# phyplugin.net
KiCad netlist of a schematic drawn in EAGLE
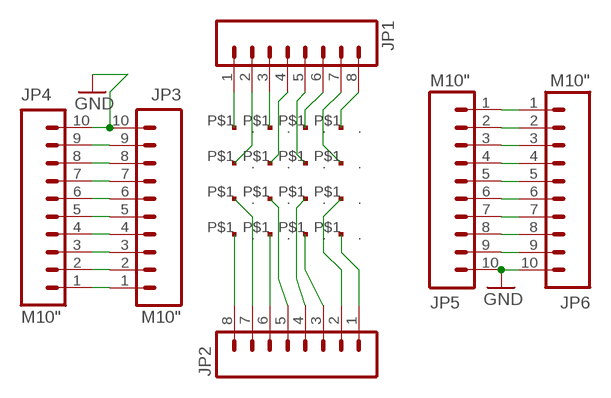
[diagram p0: schematic, sheet 1]

(export (version "E")
  (design (tool "Eeschema 10.0.6"))
  (components
    (comp (ref "JP1")
      (value "M08")
      (footprint "eagle-import:1X08")
      (libsource (lib "eagle-import") (part "M08"))
    )
    (comp (ref "JP2")
      (value "M08")
      (footprint "eagle-import:1X08")
      (libsource (lib "eagle-import") (part "M08"))
    )
    (comp (ref "JP3")
      (value "M10\"")
      (footprint "eagle-import:1X10")
      (libsource (lib "eagle-import") (part "M10{dblquote}"))
    )
    (comp (ref "JP4")
      (value "M10\"")
      (footprint "eagle-import:1X10")
      (libsource (lib "eagle-import") (part "M10{dblquote}"))
    )
    (comp (ref "JP5")
      (value "M10\"")
      (footprint "eagle-import:1X10")
      (libsource (lib "eagle-import") (part "M10{dblquote}"))
    )
    (comp (ref "JP6")
      (value "M10\"")
      (footprint "eagle-import:1X10")
      (libsource (lib "eagle-import") (part "M10{dblquote}"))
    )
    (comp (ref "U$1")
      (value "MEAPAD")
      (footprint "eagle-import:MEAPAD1MM")
      (libsource (lib "eagle-import") (part "MEAPAD"))
    )
    (comp (ref "U$2")
      (value "MEAPAD")
      (footprint "eagle-import:MEAPAD1MM")
      (libsource (lib "eagle-import") (part "MEAPAD"))
    )
    (comp (ref "U$3")
      (value "MEAPAD")
      (footprint "eagle-import:MEAPAD1MM")
      (libsource (lib "eagle-import") (part "MEAPAD"))
    )
    (comp (ref "U$4")
      (value "MEAPAD")
      (footprint "eagle-import:MEAPAD1MM")
      (libsource (lib "eagle-import") (part "MEAPAD"))
    )
    (comp (ref "U$5")
      (value "MEAPAD")
      (footprint "eagle-import:MEAPAD1MM")
      (libsource (lib "eagle-import") (part "MEAPAD"))
    )
    (comp (ref "U$6")
      (value "MEAPAD")
      (footprint "eagle-import:MEAPAD1MM")
      (libsource (lib "eagle-import") (part "MEAPAD"))
    )
    (comp (ref "U$7")
      (value "MEAPAD")
      (footprint "eagle-import:MEAPAD1MM")
      (libsource (lib "eagle-import") (part "MEAPAD"))
    )
    (comp (ref "U$8")
      (value "MEAPAD")
      (footprint "eagle-import:MEAPAD1MM")
      (libsource (lib "eagle-import") (part "MEAPAD"))
    )
    (comp (ref "U$9")
      (value "MEAPAD")
      (footprint "eagle-import:MEAPAD1MM")
      (libsource (lib "eagle-import") (part "MEAPAD"))
    )
    (comp (ref "U$10")
      (value "MEAPAD")
      (footprint "eagle-import:MEAPAD1MM")
      (libsource (lib "eagle-import") (part "MEAPAD"))
    )
    (comp (ref "U$11")
      (value "MEAPAD")
      (footprint "eagle-import:MEAPAD1MM")
      (libsource (lib "eagle-import") (part "MEAPAD"))
    )
    (comp (ref "U$12")
      (value "MEAPAD")
      (footprint "eagle-import:MEAPAD1MM")
      (libsource (lib "eagle-import") (part "MEAPAD"))
    )
    (comp (ref "U$13")
      (value "MEAPAD")
      (footprint "eagle-import:MEAPAD1MM")
      (libsource (lib "eagle-import") (part "MEAPAD"))
    )
    (comp (ref "U$14")
      (value "MEAPAD")
      (footprint "eagle-import:MEAPAD1MM")
      (libsource (lib "eagle-import") (part "MEAPAD"))
    )
    (comp (ref "U$15")
      (value "MEAPAD")
      (footprint "eagle-import:MEAPAD1MM")
      (libsource (lib "eagle-import") (part "MEAPAD"))
    )
    (comp (ref "U$16")
      (value "MEAPAD")
      (footprint "eagle-import:MEAPAD1MM")
      (libsource (lib "eagle-import") (part "MEAPAD"))
    )
  )
  (nets
    (net (code "1") (name "GND") (class "Default")
      (node (ref "JP3") (pin "10") (pinfunction "10_10") (pintype "passive"))
      (node (ref "JP4") (pin "10") (pinfunction "10_10") (pintype "passive"))
      (node (ref "JP5") (pin "10") (pinfunction "10_10") (pintype "passive"))
      (node (ref "JP6") (pin "10") (pinfunction "10_10") (pintype "passive"))
    )
    (net (code "2") (name "Net-(JP3-Pad1)") (class "Default")
      (node (ref "JP3") (pin "1") (pinfunction "1_1") (pintype "passive"))
      (node (ref "JP4") (pin "1") (pinfunction "1_1") (pintype "passive"))
    )
    (net (code "3") (name "Net-(JP3-Pad2)") (class "Default")
      (node (ref "JP3") (pin "2") (pinfunction "2_2") (pintype "passive"))
      (node (ref "JP4") (pin "2") (pinfunction "2_2") (pintype "passive"))
    )
    (net (code "4") (name "Net-(JP3-Pad3)") (class "Default")
      (node (ref "JP3") (pin "3") (pinfunction "3_3") (pintype "passive"))
      (node (ref "JP4") (pin "3") (pinfunction "3_3") (pintype "passive"))
    )
    (net (code "5") (name "Net-(JP3-Pad4)") (class "Default")
      (node (ref "JP3") (pin "4") (pinfunction "4_4") (pintype "passive"))
      (node (ref "JP4") (pin "4") (pinfunction "4_4") (pintype "passive"))
    )
    (net (code "6") (name "Net-(JP3-Pad5)") (class "Default")
      (node (ref "JP3") (pin "5") (pinfunction "5_5") (pintype "passive"))
      (node (ref "JP4") (pin "5") (pinfunction "5_5") (pintype "passive"))
    )
    (net (code "7") (name "Net-(JP3-Pad6)") (class "Default")
      (node (ref "JP3") (pin "6") (pinfunction "6_6") (pintype "passive"))
      (node (ref "JP4") (pin "6") (pinfunction "6_6") (pintype "passive"))
    )
    (net (code "8") (name "Net-(JP3-Pad7)") (class "Default")
      (node (ref "JP3") (pin "7") (pinfunction "7_7") (pintype "passive"))
      (node (ref "JP4") (pin "7") (pinfunction "7_7") (pintype "passive"))
    )
    (net (code "9") (name "Net-(JP3-Pad8)") (class "Default")
      (node (ref "JP3") (pin "8") (pinfunction "8_8") (pintype "passive"))
      (node (ref "JP4") (pin "8") (pinfunction "8_8") (pintype "passive"))
    )
    (net (code "10") (name "Net-(JP3-Pad9)") (class "Default")
      (node (ref "JP3") (pin "9") (pinfunction "9_9") (pintype "passive"))
      (node (ref "JP4") (pin "9") (pinfunction "9_9") (pintype "passive"))
    )
    (net (code "11") (name "Net-(JP5-Pad1)") (class "Default")
      (node (ref "JP5") (pin "1") (pinfunction "1_1") (pintype "passive"))
      (node (ref "JP6") (pin "1") (pinfunction "1_1") (pintype "passive"))
    )
    (net (code "12") (name "Net-(JP5-Pad2)") (class "Default")
      (node (ref "JP5") (pin "2") (pinfunction "2_2") (pintype "passive"))
      (node (ref "JP6") (pin "2") (pinfunction "2_2") (pintype "passive"))
    )
    (net (code "13") (name "Net-(JP5-Pad3)") (class "Default")
      (node (ref "JP5") (pin "3") (pinfunction "3_3") (pintype "passive"))
      (node (ref "JP6") (pin "3") (pinfunction "3_3") (pintype "passive"))
    )
    (net (code "14") (name "Net-(JP5-Pad4)") (class "Default")
      (node (ref "JP5") (pin "4") (pinfunction "4_4") (pintype "passive"))
      (node (ref "JP6") (pin "4") (pinfunction "4_4") (pintype "passive"))
    )
    (net (code "15") (name "Net-(JP5-Pad5)") (class "Default")
      (node (ref "JP5") (pin "5") (pinfunction "5_5") (pintype "passive"))
      (node (ref "JP6") (pin "5") (pinfunction "5_5") (pintype "passive"))
    )
    (net (code "16") (name "Net-(JP5-Pad6)") (class "Default")
      (node (ref "JP5") (pin "6") (pinfunction "6_6") (pintype "passive"))
      (node (ref "JP6") (pin "6") (pinfunction "6_6") (pintype "passive"))
    )
    (net (code "17") (name "Net-(JP5-Pad7)") (class "Default")
      (node (ref "JP5") (pin "7") (pinfunction "7_7") (pintype "passive"))
      (node (ref "JP6") (pin "7") (pinfunction "7_7") (pintype "passive"))
    )
    (net (code "18") (name "Net-(JP5-Pad8)") (class "Default")
      (node (ref "JP5") (pin "8") (pinfunction "8_8") (pintype "passive"))
      (node (ref "JP6") (pin "8") (pinfunction "8_8") (pintype "passive"))
    )
    (net (code "19") (name "Net-(JP5-Pad9)") (class "Default")
      (node (ref "JP5") (pin "9") (pinfunction "9_9") (pintype "passive"))
      (node (ref "JP6") (pin "9") (pinfunction "9_9") (pintype "passive"))
    )
    (net (code "20") (name "Net-(U$1-.)") (class "Default")
      (node (ref "JP1") (pin "1") (pinfunction "1_1") (pintype "passive"))
      (node (ref "U$1") (pin "P$1") (pinfunction "._P$1") (pintype "bidirectional"))
    )
    (net (code "21") (name "Net-(U$2-.)") (class "Default")
      (node (ref "JP1") (pin "3") (pinfunction "3_3") (pintype "passive"))
      (node (ref "U$2") (pin "P$1") (pinfunction "._P$1") (pintype "bidirectional"))
    )
    (net (code "22") (name "Net-(U$3-.)") (class "Default")
      (node (ref "JP1") (pin "6") (pinfunction "6_6") (pintype "passive"))
      (node (ref "U$3") (pin "P$1") (pinfunction "._P$1") (pintype "bidirectional"))
    )
    (net (code "23") (name "Net-(U$4-.)") (class "Default")
      (node (ref "JP1") (pin "8") (pinfunction "8_8") (pintype "passive"))
      (node (ref "U$4") (pin "P$1") (pinfunction "._P$1") (pintype "bidirectional"))
    )
    (net (code "24") (name "Net-(U$5-.)") (class "Default")
      (node (ref "JP1") (pin "2") (pinfunction "2_2") (pintype "passive"))
      (node (ref "U$5") (pin "P$1") (pinfunction "._P$1") (pintype "bidirectional"))
    )
    (net (code "25") (name "Net-(U$6-.)") (class "Default")
      (node (ref "JP1") (pin "4") (pinfunction "4_4") (pintype "passive"))
      (node (ref "U$6") (pin "P$1") (pinfunction "._P$1") (pintype "bidirectional"))
    )
    (net (code "26") (name "Net-(U$7-.)") (class "Default")
      (node (ref "JP1") (pin "5") (pinfunction "5_5") (pintype "passive"))
      (node (ref "U$7") (pin "P$1") (pinfunction "._P$1") (pintype "bidirectional"))
    )
    (net (code "27") (name "Net-(U$8-.)") (class "Default")
      (node (ref "JP1") (pin "7") (pinfunction "7_7") (pintype "passive"))
      (node (ref "U$8") (pin "P$1") (pinfunction "._P$1") (pintype "bidirectional"))
    )
    (net (code "28") (name "Net-(U$9-.)") (class "Default")
      (node (ref "JP2") (pin "7") (pinfunction "7_7") (pintype "passive"))
      (node (ref "U$9") (pin "P$1") (pinfunction "._P$1") (pintype "bidirectional"))
    )
    (net (code "29") (name "Net-(U$10-.)") (class "Default")
      (node (ref "JP2") (pin "5") (pinfunction "5_5") (pintype "passive"))
      (node (ref "U$10") (pin "P$1") (pinfunction "._P$1") (pintype "bidirectional"))
    )
    (net (code "30") (name "Net-(U$11-.)") (class "Default")
      (node (ref "JP2") (pin "4") (pinfunction "4_4") (pintype "passive"))
      (node (ref "U$11") (pin "P$1") (pinfunction "._P$1") (pintype "bidirectional"))
    )
    (net (code "31") (name "Net-(U$12-.)") (class "Default")
      (node (ref "JP2") (pin "2") (pinfunction "2_2") (pintype "passive"))
      (node (ref "U$12") (pin "P$1") (pinfunction "._P$1") (pintype "bidirectional"))
    )
    (net (code "32") (name "Net-(U$13-.)") (class "Default")
      (node (ref "JP2") (pin "8") (pinfunction "8_8") (pintype "passive"))
      (node (ref "U$13") (pin "P$1") (pinfunction "._P$1") (pintype "bidirectional"))
    )
    (net (code "33") (name "Net-(U$14-.)") (class "Default")
      (node (ref "JP2") (pin "6") (pinfunction "6_6") (pintype "passive"))
      (node (ref "U$14") (pin "P$1") (pinfunction "._P$1") (pintype "bidirectional"))
    )
    (net (code "34") (name "Net-(U$15-.)") (class "Default")
      (node (ref "JP2") (pin "3") (pinfunction "3_3") (pintype "passive"))
      (node (ref "U$15") (pin "P$1") (pinfunction "._P$1") (pintype "bidirectional"))
    )
    (net (code "35") (name "Net-(U$16-.)") (class "Default")
      (node (ref "JP2") (pin "1") (pinfunction "1_1") (pintype "passive"))
      (node (ref "U$16") (pin "P$1") (pinfunction "._P$1") (pintype "bidirectional"))
    )
  )
)
